# VariableBenchPowerSupply.net
KiCad netlist of a schematic drawn in Altium Designer
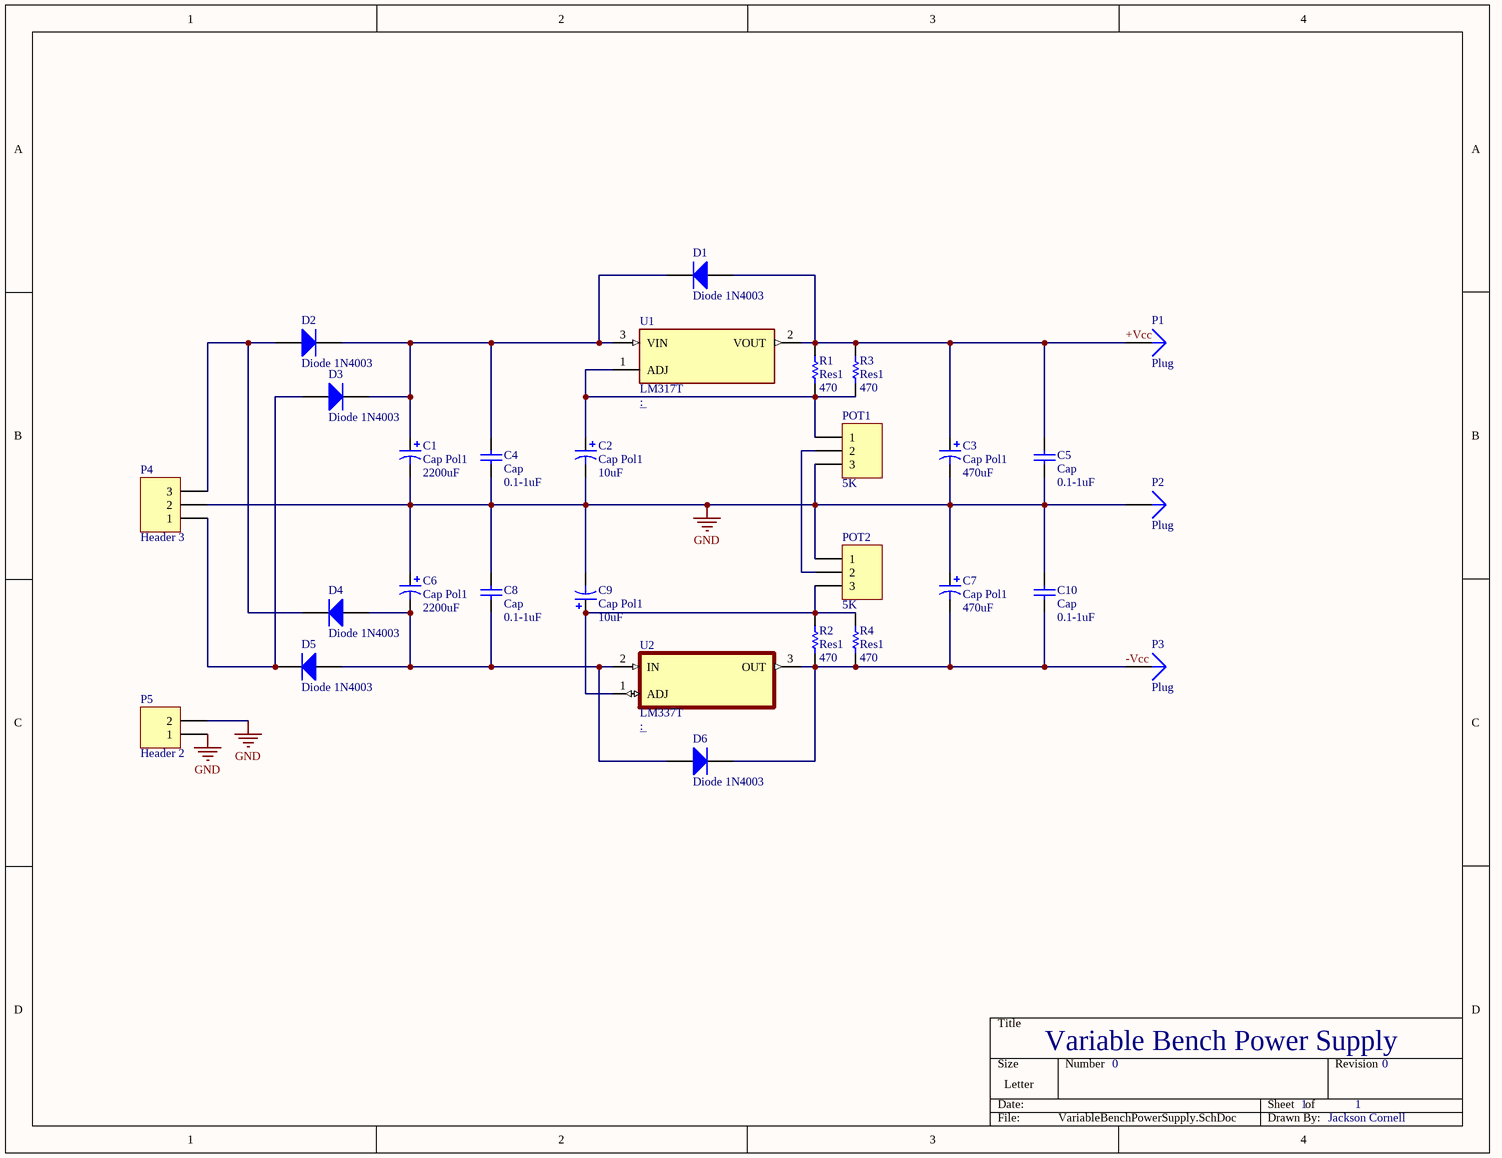
[diagram p0: VariableBenchPowerSupply.SchDoc]

(export (version "E")
  (design (tool "Eeschema 10.0.6"))
  (components
    (comp (ref "C1")
      (value "Cap Pol1")
      (footprint "CAPR5-4X5")
      (description "Polarized Capacitor (Radial)")
      (fields (field (name "ALTIUM_VALUE") "2200uF") (field (name "PUBLISHER") "Altium Limited"))
      (libsource (lib "Miscellaneous Devices") (part "Cap Pol1"))
    )
    (comp (ref "C2")
      (value "Cap Pol1")
      (footprint "CAPR5-4X5")
      (description "Polarized Capacitor (Radial)")
      (fields (field (name "ALTIUM_VALUE") "10uF") (field (name "PUBLISHER") "Altium Limited"))
      (libsource (lib "Miscellaneous Devices") (part "Cap Pol1"))
    )
    (comp (ref "C3")
      (value "Cap Pol1")
      (footprint "CAPR5-4X5")
      (description "Polarized Capacitor (Radial)")
      (fields (field (name "ALTIUM_VALUE") "470uF") (field (name "PUBLISHER") "Altium Limited"))
      (libsource (lib "Miscellaneous Devices") (part "Cap Pol1"))
    )
    (comp (ref "C4")
      (value "Cap")
      (footprint "RAD-0.3")
      (description "Capacitor")
      (fields (field (name "ALTIUM_VALUE") "0.1-1uF") (field (name "PUBLISHER") "Altium Limited"))
      (libsource (lib "Miscellaneous Devices") (part "Cap"))
    )
    (comp (ref "C5")
      (value "Cap")
      (footprint "RAD-0.3")
      (description "Capacitor")
      (fields (field (name "ALTIUM_VALUE") "0.1-1uF") (field (name "PUBLISHER") "Altium Limited"))
      (libsource (lib "Miscellaneous Devices") (part "Cap"))
    )
    (comp (ref "C6")
      (value "Cap Pol1")
      (footprint "CAPR5-4X5")
      (description "Polarized Capacitor (Radial)")
      (fields (field (name "ALTIUM_VALUE") "2200uF") (field (name "PUBLISHER") "Altium Limited"))
      (libsource (lib "Miscellaneous Devices") (part "Cap Pol1"))
    )
    (comp (ref "C7")
      (value "Cap Pol1")
      (footprint "CAPR5-4X5")
      (description "Polarized Capacitor (Radial)")
      (fields (field (name "ALTIUM_VALUE") "470uF") (field (name "PUBLISHER") "Altium Limited"))
      (libsource (lib "Miscellaneous Devices") (part "Cap Pol1"))
    )
    (comp (ref "C8")
      (value "Cap")
      (footprint "RAD-0.3")
      (description "Capacitor")
      (fields (field (name "ALTIUM_VALUE") "0.1-1uF") (field (name "PUBLISHER") "Altium Limited"))
      (libsource (lib "Miscellaneous Devices") (part "Cap"))
    )
    (comp (ref "C9")
      (value "Cap Pol1")
      (footprint "CAPR5-4X5")
      (description "Polarized Capacitor (Radial)")
      (fields (field (name "ALTIUM_VALUE") "10uF") (field (name "PUBLISHER") "Altium Limited"))
      (libsource (lib "Miscellaneous Devices") (part "Cap Pol1"))
    )
    (comp (ref "C10")
      (value "Cap")
      (footprint "RAD-0.3")
      (description "Capacitor")
      (fields (field (name "ALTIUM_VALUE") "0.1-1uF") (field (name "PUBLISHER") "Altium Limited"))
      (libsource (lib "Miscellaneous Devices") (part "Cap"))
    )
    (comp (ref "D1")
      (value "Diode 1N4003")
      (footprint "DO-41")
      (description "1 Amp General Purpose Rectifier")
      (fields (field (name "PUBLISHER") "Altium Limited"))
      (libsource (lib "Miscellaneous Devices") (part "Diode 1N4003"))
    )
    (comp (ref "D2")
      (value "Diode 1N4003")
      (footprint "DO-41")
      (description "1 Amp General Purpose Rectifier")
      (fields (field (name "PUBLISHER") "Altium Limited"))
      (libsource (lib "Miscellaneous Devices") (part "Diode 1N4003"))
    )
    (comp (ref "D3")
      (value "Diode 1N4003")
      (footprint "DO-41")
      (description "1 Amp General Purpose Rectifier")
      (fields (field (name "PUBLISHER") "Altium Limited"))
      (libsource (lib "Miscellaneous Devices") (part "Diode 1N4003"))
    )
    (comp (ref "D4")
      (value "Diode 1N4003")
      (footprint "DO-41")
      (description "1 Amp General Purpose Rectifier")
      (fields (field (name "PUBLISHER") "Altium Limited"))
      (libsource (lib "Miscellaneous Devices") (part "Diode 1N4003"))
    )
    (comp (ref "D5")
      (value "Diode 1N4003")
      (footprint "DO-41")
      (description "1 Amp General Purpose Rectifier")
      (fields (field (name "PUBLISHER") "Altium Limited"))
      (libsource (lib "Miscellaneous Devices") (part "Diode 1N4003"))
    )
    (comp (ref "D6")
      (value "Diode 1N4003")
      (footprint "DO-41")
      (description "1 Amp General Purpose Rectifier")
      (fields (field (name "PUBLISHER") "Altium Limited"))
      (libsource (lib "Miscellaneous Devices") (part "Diode 1N4003"))
    )
    (comp (ref "P1")
      (value "Plug")
      (footprint "PIN1")
      (fields (field (name "PUBLISHER") "Altium Limited"))
      (libsource (lib "Miscellaneous Connectors") (part "Plug"))
    )
    (comp (ref "P2")
      (value "Plug")
      (footprint "PIN1")
      (fields (field (name "PUBLISHER") "Altium Limited"))
      (libsource (lib "Miscellaneous Connectors") (part "Plug"))
    )
    (comp (ref "P3")
      (value "Plug")
      (footprint "PIN1")
      (fields (field (name "PUBLISHER") "Altium Limited"))
      (libsource (lib "Miscellaneous Connectors") (part "Plug"))
    )
    (comp (ref "P4")
      (value "Header 3")
      (footprint "HDR1X3")
      (description "Header, 3-Pin")
      (fields (field (name "PUBLISHER") "Altium Limited"))
      (libsource (lib "") (part "Header 3_1"))
    )
    (comp (ref "P5")
      (value "Header 2")
      (footprint "HDR1X2")
      (description "Header, 2-Pin")
      (fields (field (name "PUBLISHER") "Altium Limited"))
      (libsource (lib "Miscellaneous Connectors") (part "Header 2"))
    )
    (comp (ref "POT1")
      (value "5K")
      (footprint "HDR1X3")
      (description "Header, 3-Pin")
      (fields (field (name "PUBLISHER") "Altium Limited"))
      (libsource (lib "Miscellaneous Connectors") (part "Header 3"))
    )
    (comp (ref "POT2")
      (value "5K")
      (footprint "HDR1X3")
      (description "Header, 3-Pin")
      (fields (field (name "PUBLISHER") "Altium Limited"))
      (libsource (lib "Miscellaneous Connectors") (part "Header 3"))
    )
    (comp (ref "R1")
      (value "Res1")
      (footprint "AXIAL-0.3")
      (description "Resistor")
      (fields (field (name "ALTIUM_VALUE") "470") (field (name "PUBLISHER") "Altium Limited"))
      (libsource (lib "Miscellaneous Devices") (part "Res1"))
    )
    (comp (ref "R2")
      (value "Res1")
      (footprint "AXIAL-0.3")
      (description "Resistor")
      (fields (field (name "ALTIUM_VALUE") "470") (field (name "PUBLISHER") "Altium Limited"))
      (libsource (lib "Miscellaneous Devices") (part "Res1"))
    )
    (comp (ref "R3")
      (value "Res1")
      (footprint "AXIAL-0.3")
      (description "Resistor")
      (fields (field (name "ALTIUM_VALUE") "470") (field (name "PUBLISHER") "Altium Limited"))
      (libsource (lib "Miscellaneous Devices") (part "Res1"))
    )
    (comp (ref "R4")
      (value "Res1")
      (footprint "AXIAL-0.3")
      (description "Resistor")
      (fields (field (name "ALTIUM_VALUE") "470") (field (name "PUBLISHER") "Altium Limited"))
      (libsource (lib "Miscellaneous Devices") (part "Res1"))
    )
    (comp (ref "U1")
      (value "LM317T")
      (footprint "TO254P1054X470X1955-3")
      (description "1.5-A, 40-V, adjustable linear voltage regulator 3-TO-220 0 to 125")
      (fields (field (name "MF") "Texas Instruments") (field (name "MP") "LM317T/NOPB"))
      (libsource (lib "LM317T_NOPB") (part "LM317T/NOPB"))
    )
    (comp (ref "U2")
      (value "LM337T")
      (footprint "TO254P1054X470X1955-3")
      (description "Linear Voltage Regulator IC 1 Output 1.5A TO-220AB")
      (fields (field (name "MF") "ON Semiconductor"))
      (libsource (lib "LM337T") (part "LM337T"))
    )
  )
  (nets
    (net (code "1") (name "/+Vcc") (class "Default")
      (node (ref "C3") (pin "1") (pinfunction "1_1") (pintype "passive"))
      (node (ref "C5") (pin "1") (pinfunction "1_1") (pintype "passive"))
      (node (ref "D1") (pin "1") (pinfunction "A_1") (pintype "passive"))
      (node (ref "P1") (pin "1") (pinfunction "1_1") (pintype "passive"))
      (node (ref "R1") (pin "2") (pinfunction "2_2") (pintype "passive"))
      (node (ref "R3") (pin "2") (pinfunction "2_2") (pintype "passive"))
      (node (ref "U1") (pin "2") (pinfunction "VOUT_2") (pintype "output"))
    )
    (net (code "2") (name "/-Vcc") (class "Default")
      (node (ref "C10") (pin "2") (pinfunction "2_2") (pintype "passive"))
      (node (ref "C7") (pin "2") (pinfunction "2_2") (pintype "passive"))
      (node (ref "D6") (pin "2") (pinfunction "K_2") (pintype "passive"))
      (node (ref "P3") (pin "1") (pinfunction "1_1") (pintype "passive"))
      (node (ref "R2") (pin "1") (pinfunction "1_1") (pintype "passive"))
      (node (ref "R4") (pin "1") (pinfunction "1_1") (pintype "passive"))
      (node (ref "U2") (pin "3") (pinfunction "OUT_3") (pintype "output"))
    )
    (net (code "3") (name "GND") (class "Default")
      (node (ref "C1") (pin "2") (pinfunction "2_2") (pintype "passive"))
      (node (ref "C10") (pin "1") (pinfunction "1_1") (pintype "passive"))
      (node (ref "C2") (pin "2") (pinfunction "2_2") (pintype "passive"))
      (node (ref "C3") (pin "2") (pinfunction "2_2") (pintype "passive"))
      (node (ref "C4") (pin "1") (pinfunction "1_1") (pintype "passive"))
      (node (ref "C5") (pin "2") (pinfunction "2_2") (pintype "passive"))
      (node (ref "C6") (pin "1") (pinfunction "1_1") (pintype "passive"))
      (node (ref "C7") (pin "1") (pinfunction "1_1") (pintype "passive"))
      (node (ref "C8") (pin "2") (pinfunction "2_2") (pintype "passive"))
      (node (ref "C9") (pin "2") (pinfunction "2_2") (pintype "passive"))
      (node (ref "P2") (pin "1") (pinfunction "1_1") (pintype "passive"))
      (node (ref "P4") (pin "2") (pinfunction "2_2") (pintype "passive"))
      (node (ref "P5") (pin "1") (pinfunction "1_1") (pintype "passive"))
      (node (ref "P5") (pin "2") (pinfunction "2_2") (pintype "passive"))
      (node (ref "POT1") (pin "3") (pinfunction "3_3") (pintype "passive"))
      (node (ref "POT2") (pin "1") (pinfunction "1_1") (pintype "passive"))
    )
    (net (code "4") (name "Net-(D1-K)") (class "Default")
      (node (ref "C1") (pin "1") (pinfunction "1_1") (pintype "passive"))
      (node (ref "C4") (pin "2") (pinfunction "2_2") (pintype "passive"))
      (node (ref "D1") (pin "2") (pinfunction "K_2") (pintype "passive"))
      (node (ref "D2") (pin "2") (pinfunction "K_2") (pintype "passive"))
      (node (ref "D3") (pin "2") (pinfunction "K_2") (pintype "passive"))
      (node (ref "U1") (pin "3") (pinfunction "VIN_3") (pintype "input"))
    )
    (net (code "5") (name "Net-(D2-A)") (class "Default")
      (node (ref "D2") (pin "1") (pinfunction "A_1") (pintype "passive"))
      (node (ref "D4") (pin "2") (pinfunction "K_2") (pintype "passive"))
      (node (ref "P4") (pin "3") (pinfunction "3_3") (pintype "passive"))
    )
    (net (code "6") (name "Net-(D3-A)") (class "Default")
      (node (ref "D3") (pin "1") (pinfunction "A_1") (pintype "passive"))
      (node (ref "D5") (pin "2") (pinfunction "K_2") (pintype "passive"))
      (node (ref "P4") (pin "1") (pinfunction "1_1") (pintype "passive"))
    )
    (net (code "7") (name "Net-(D4-A)") (class "Default")
      (node (ref "C6") (pin "2") (pinfunction "2_2") (pintype "passive"))
      (node (ref "C8") (pin "1") (pinfunction "1_1") (pintype "passive"))
      (node (ref "D4") (pin "1") (pinfunction "A_1") (pintype "passive"))
      (node (ref "D5") (pin "1") (pinfunction "A_1") (pintype "passive"))
      (node (ref "D6") (pin "1") (pinfunction "A_1") (pintype "passive"))
      (node (ref "U2") (pin "2") (pinfunction "IN_2") (pintype "input"))
    )
    (net (code "8") (name "Net-(POT1-Pad2)") (class "Default")
      (node (ref "POT1") (pin "2") (pinfunction "2_2") (pintype "passive"))
      (node (ref "POT2") (pin "2") (pinfunction "2_2") (pintype "passive"))
    )
    (net (code "9") (name "Net-(U1-ADJ)") (class "Default")
      (node (ref "C2") (pin "1") (pinfunction "1_1") (pintype "passive"))
      (node (ref "POT1") (pin "1") (pinfunction "1_1") (pintype "passive"))
      (node (ref "R1") (pin "1") (pinfunction "1_1") (pintype "passive"))
      (node (ref "R3") (pin "1") (pinfunction "1_1") (pintype "passive"))
      (node (ref "U1") (pin "1") (pinfunction "ADJ_1") (pintype "passive"))
    )
    (net (code "10") (name "Net-(U2-ADJ)") (class "Default")
      (node (ref "C9") (pin "1") (pinfunction "1_1") (pintype "passive"))
      (node (ref "POT2") (pin "3") (pinfunction "3_3") (pintype "passive"))
      (node (ref "R2") (pin "2") (pinfunction "2_2") (pintype "passive"))
      (node (ref "R4") (pin "2") (pinfunction "2_2") (pintype "passive"))
      (node (ref "U2") (pin "1") (pinfunction "ADJ_1") (pintype "bidirectional"))
    )
  )
)
